# DETECTOR01.net
KiCad netlist of a schematic drawn in EAGLE
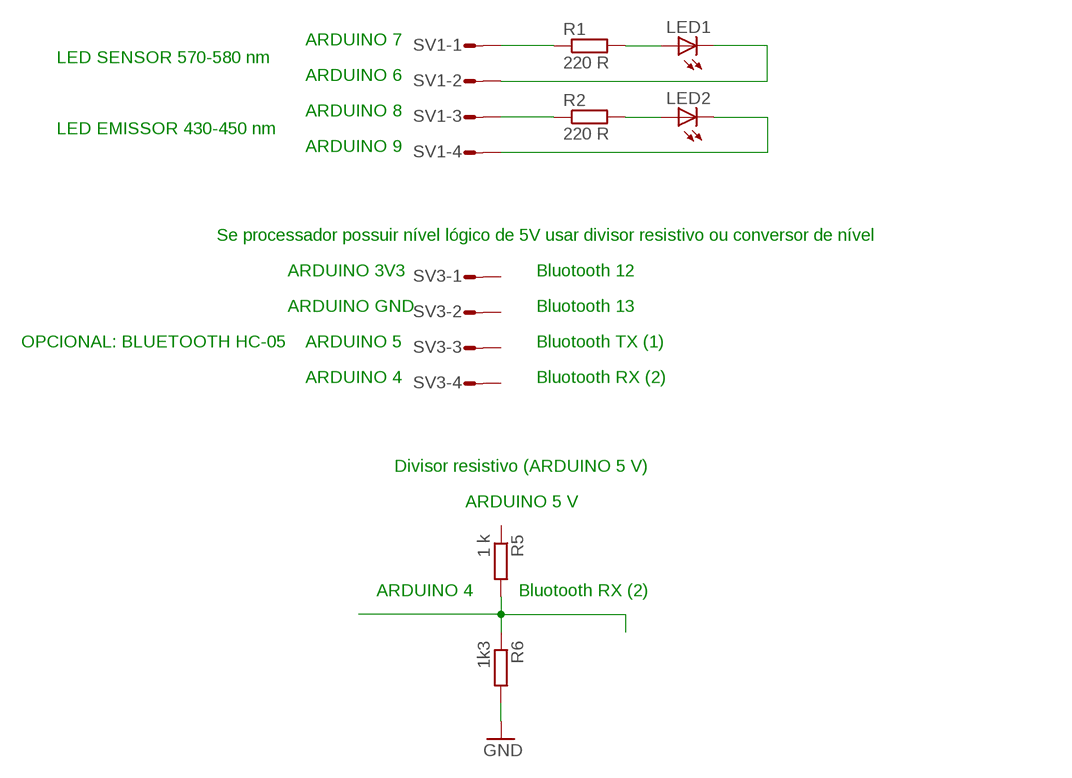
[diagram p0: schematic, sheet 1]

(export (version "E")
  (design (tool "Eeschema 10.0.6"))
  (components
    (comp (ref "LED1")
      (value "LED5MM")
      (footprint "eagle-import:LED5MM")
      (libsource (lib "eagle-import") (part "LED5MM"))
    )
    (comp (ref "LED2")
      (value "LED5MM")
      (footprint "eagle-import:LED5MM")
      (libsource (lib "eagle-import") (part "LED5MM"))
    )
    (comp (ref "R1")
      (value "220 R")
      (footprint "eagle-import:0204_7")
      (libsource (lib "eagle-import") (part "R-EU_0204/7"))
    )
    (comp (ref "R2")
      (value "220 R")
      (footprint "eagle-import:0204_7")
      (libsource (lib "eagle-import") (part "R-EU_0204/7"))
    )
    (comp (ref "R5")
      (value "1 k")
      (footprint "eagle-import:0204_7")
      (libsource (lib "eagle-import") (part "R-EU_0204/7"))
    )
    (comp (ref "R6")
      (value "1k3")
      (footprint "eagle-import:0204_7")
      (libsource (lib "eagle-import") (part "R-EU_0204/7"))
    )
    (comp (ref "SV1")
      (value "L04P")
      (footprint "eagle-import:L04P")
      (libsource (lib "eagle-import") (part "L04P"))
    )
    (comp (ref "SV3")
      (value "L04P")
      (footprint "eagle-import:L04P")
      (libsource (lib "eagle-import") (part "L04P"))
    )
  )
  (nets
    (net (code "1") (name "GND") (class "Default")
      (node (ref "R6") (pin "2") (pinfunction "2_2") (pintype "passive"))
    )
    (net (code "2") (name "Net-(LED1-C)") (class "Default")
      (node (ref "LED1") (pin "K") (pinfunction "C_K") (pintype "passive"))
      (node (ref "SV1") (pin "2") (pinfunction "S_2") (pintype "passive"))
    )
    (net (code "3") (name "Net-(LED1-PadA)") (class "Default")
      (node (ref "LED1") (pin "A") (pinfunction "A_A") (pintype "passive"))
      (node (ref "R1") (pin "2") (pinfunction "2_2") (pintype "passive"))
    )
    (net (code "4") (name "Net-(LED2-C)") (class "Default")
      (node (ref "LED2") (pin "K") (pinfunction "C_K") (pintype "passive"))
      (node (ref "SV1") (pin "4") (pinfunction "S_4") (pintype "passive"))
    )
    (net (code "5") (name "Net-(LED2-PadA)") (class "Default")
      (node (ref "LED2") (pin "A") (pinfunction "A_A") (pintype "passive"))
      (node (ref "R2") (pin "2") (pinfunction "2_2") (pintype "passive"))
    )
    (net (code "6") (name "Net-(R5-Pad2)") (class "Default")
      (node (ref "R5") (pin "2") (pinfunction "2_2") (pintype "passive"))
      (node (ref "R6") (pin "1") (pinfunction "1_1") (pintype "passive"))
    )
    (net (code "7") (name "Net-(SV1A-S)") (class "Default")
      (node (ref "R1") (pin "1") (pinfunction "1_1") (pintype "passive"))
      (node (ref "SV1") (pin "1") (pinfunction "S_1") (pintype "passive"))
    )
    (net (code "8") (name "Net-(SV1C-S)") (class "Default")
      (node (ref "R2") (pin "1") (pinfunction "1_1") (pintype "passive"))
      (node (ref "SV1") (pin "3") (pinfunction "S_3") (pintype "passive"))
    )
    (net (code "9") (name "unconnected-(R5-Pad1)") (class "Default")
      (node (ref "R5") (pin "1") (pinfunction "1_1") (pintype "passive"))
    )
    (net (code "10") (name "unconnected-(SV3A-S-Pad1)") (class "Default")
      (node (ref "SV3") (pin "1") (pinfunction "S_1") (pintype "passive"))
    )
    (net (code "11") (name "unconnected-(SV3B-S-Pad2)") (class "Default")
      (node (ref "SV3") (pin "2") (pinfunction "S_2") (pintype "passive"))
    )
    (net (code "12") (name "unconnected-(SV3C-S-Pad3)") (class "Default")
      (node (ref "SV3") (pin "3") (pinfunction "S_3") (pintype "passive"))
    )
    (net (code "13") (name "unconnected-(SV3D-S-Pad4)") (class "Default")
      (node (ref "SV3") (pin "4") (pinfunction "S_4") (pintype "passive"))
    )
  )
)
